# SensorDesign.net
KiCad netlist of a schematic drawn in Altium Designer
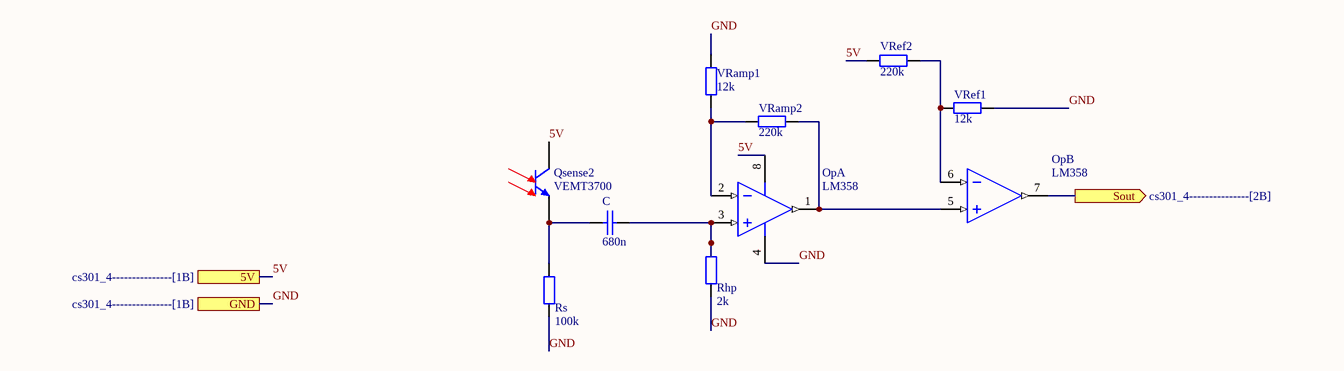
[diagram p0: SensorDesign.SchDoc]

(export (version "E")
  (design (tool "Eeschema 10.0.6"))
  (components
    (comp (ref "C")
      (value "680n")
      (footprint "0805 CAP")
      (description "SMT ceramic capacitor 0805 size")
      (libsource (lib "EE209_Library") (part "CerCap_SMT_0805"))
    )
    (comp (ref "Op")
      (value "LM358")
      (footprint "SO - 8")
      (description "IC OPAMP 8SOIC")
      (libsource (lib "EE209_Library") (part "LM358_SMT_SOIC8"))
    )
    (comp (ref "Qsense2")
      (value "VEMT3700")
      (footprint "VEMT3700")
      (description "Silicon NPN Phototransistor")
      (libsource (lib "COMSYS301") (part "VEMT3700"))
    )
    (comp (ref "Rhp")
      (value "2k")
      (footprint "0805 RES")
      (description "0805 resistor")
      (fields (field (name "PUBLISHER") "Altium Limited"))
      (libsource (lib "") (part "Res_SMT_0805_1"))
    )
    (comp (ref "Rs")
      (value "100k")
      (footprint "0805 RES")
      (description "0805 resistor")
      (fields (field (name "PUBLISHER") "Altium Limited"))
      (libsource (lib "") (part "Res_SMT_0805_1"))
    )
    (comp (ref "VRamp1")
      (value "12k")
      (footprint "0805 RES")
      (description "0805 resistor")
      (fields (field (name "PUBLISHER") "Altium Limited"))
      (libsource (lib "") (part "Res_SMT_0805_2"))
    )
    (comp (ref "VRamp2")
      (value "220k")
      (footprint "0805 RES")
      (description "0805 resistor")
      (fields (field (name "Comment") "Res_SMT_0805") (field (name "PUBLISHER") "Altium Limited"))
      (libsource (lib "University of Auckland") (part "Res_SMT_0805"))
    )
    (comp (ref "VRef1")
      (value "12k")
      (footprint "0805 RES")
      (description "0805 resistor")
      (fields (field (name "PUBLISHER") "Altium Limited"))
      (libsource (lib "EE209_Library") (part "Res_SMT_0805"))
    )
    (comp (ref "VRef2")
      (value "220k")
      (footprint "0805 RES")
      (description "0805 resistor")
      (fields (field (name "PUBLISHER") "Altium Limited"))
      (libsource (lib "EE209_Library") (part "Res_SMT_0805"))
    )
  )
  (nets
    (net (code "1") (name "/5V") (class "Default")
      (node (ref "Op") (pin "8") (pinfunction "VDD_8") (pintype "power_in"))
      (node (ref "Qsense2") (pin "1") (pinfunction "C_1") (pintype "passive"))
      (node (ref "VRef2") (pin "1") (pinfunction "1_1") (pintype "passive"))
    )
    (net (code "2") (name "/GND") (class "Default")
      (node (ref "Op") (pin "4") (pinfunction "VSS_4") (pintype "power_in"))
      (node (ref "Rhp") (pin "2") (pinfunction "2_2") (pintype "passive"))
      (node (ref "Rs") (pin "2") (pinfunction "2_2") (pintype "passive"))
      (node (ref "VRamp1") (pin "2") (pinfunction "2_2") (pintype "passive"))
      (node (ref "VRef1") (pin "2") (pinfunction "2_2") (pintype "passive"))
    )
    (net (code "3") (name "/Sout") (class "Default")
      (node (ref "Op") (pin "7") (pinfunction "VOUTA_7") (pintype "output"))
    )
    (net (code "4") (name "Net-(OpA-VINA+)") (class "Default")
      (node (ref "C") (pin "2") (pinfunction "2_2") (pintype "passive"))
      (node (ref "Op") (pin "3") (pinfunction "VINA+_3") (pintype "input"))
      (node (ref "Rhp") (pin "1") (pinfunction "1_1") (pintype "passive"))
    )
    (net (code "5") (name "Net-(OpA-VINA-)") (class "Default")
      (node (ref "Op") (pin "2") (pinfunction "VINA-_2") (pintype "input"))
      (node (ref "VRamp1") (pin "1") (pinfunction "1_1") (pintype "passive"))
      (node (ref "VRamp2") (pin "1") (pinfunction "1_1") (pintype "passive"))
    )
    (net (code "6") (name "Net-(OpA-VOUTA)") (class "Default")
      (node (ref "Op") (pin "1") (pinfunction "VOUTA_1") (pintype "output"))
      (node (ref "Op") (pin "5") (pinfunction "VINA+_5") (pintype "input"))
      (node (ref "VRamp2") (pin "2") (pinfunction "2_2") (pintype "passive"))
    )
    (net (code "7") (name "Net-(OpB-VINA-)") (class "Default")
      (node (ref "Op") (pin "6") (pinfunction "VINA-_6") (pintype "input"))
      (node (ref "VRef1") (pin "1") (pinfunction "1_1") (pintype "passive"))
      (node (ref "VRef2") (pin "2") (pinfunction "2_2") (pintype "passive"))
    )
    (net (code "8") (name "Net-(Qsense2-E)") (class "Default")
      (node (ref "C") (pin "1") (pinfunction "1_1") (pintype "passive"))
      (node (ref "Qsense2") (pin "2") (pinfunction "E_2") (pintype "passive"))
      (node (ref "Rs") (pin "1") (pinfunction "1_1") (pintype "passive"))
    )
  )
)
